# ble112_shield.net
KiCad netlist of a schematic drawn in EAGLE
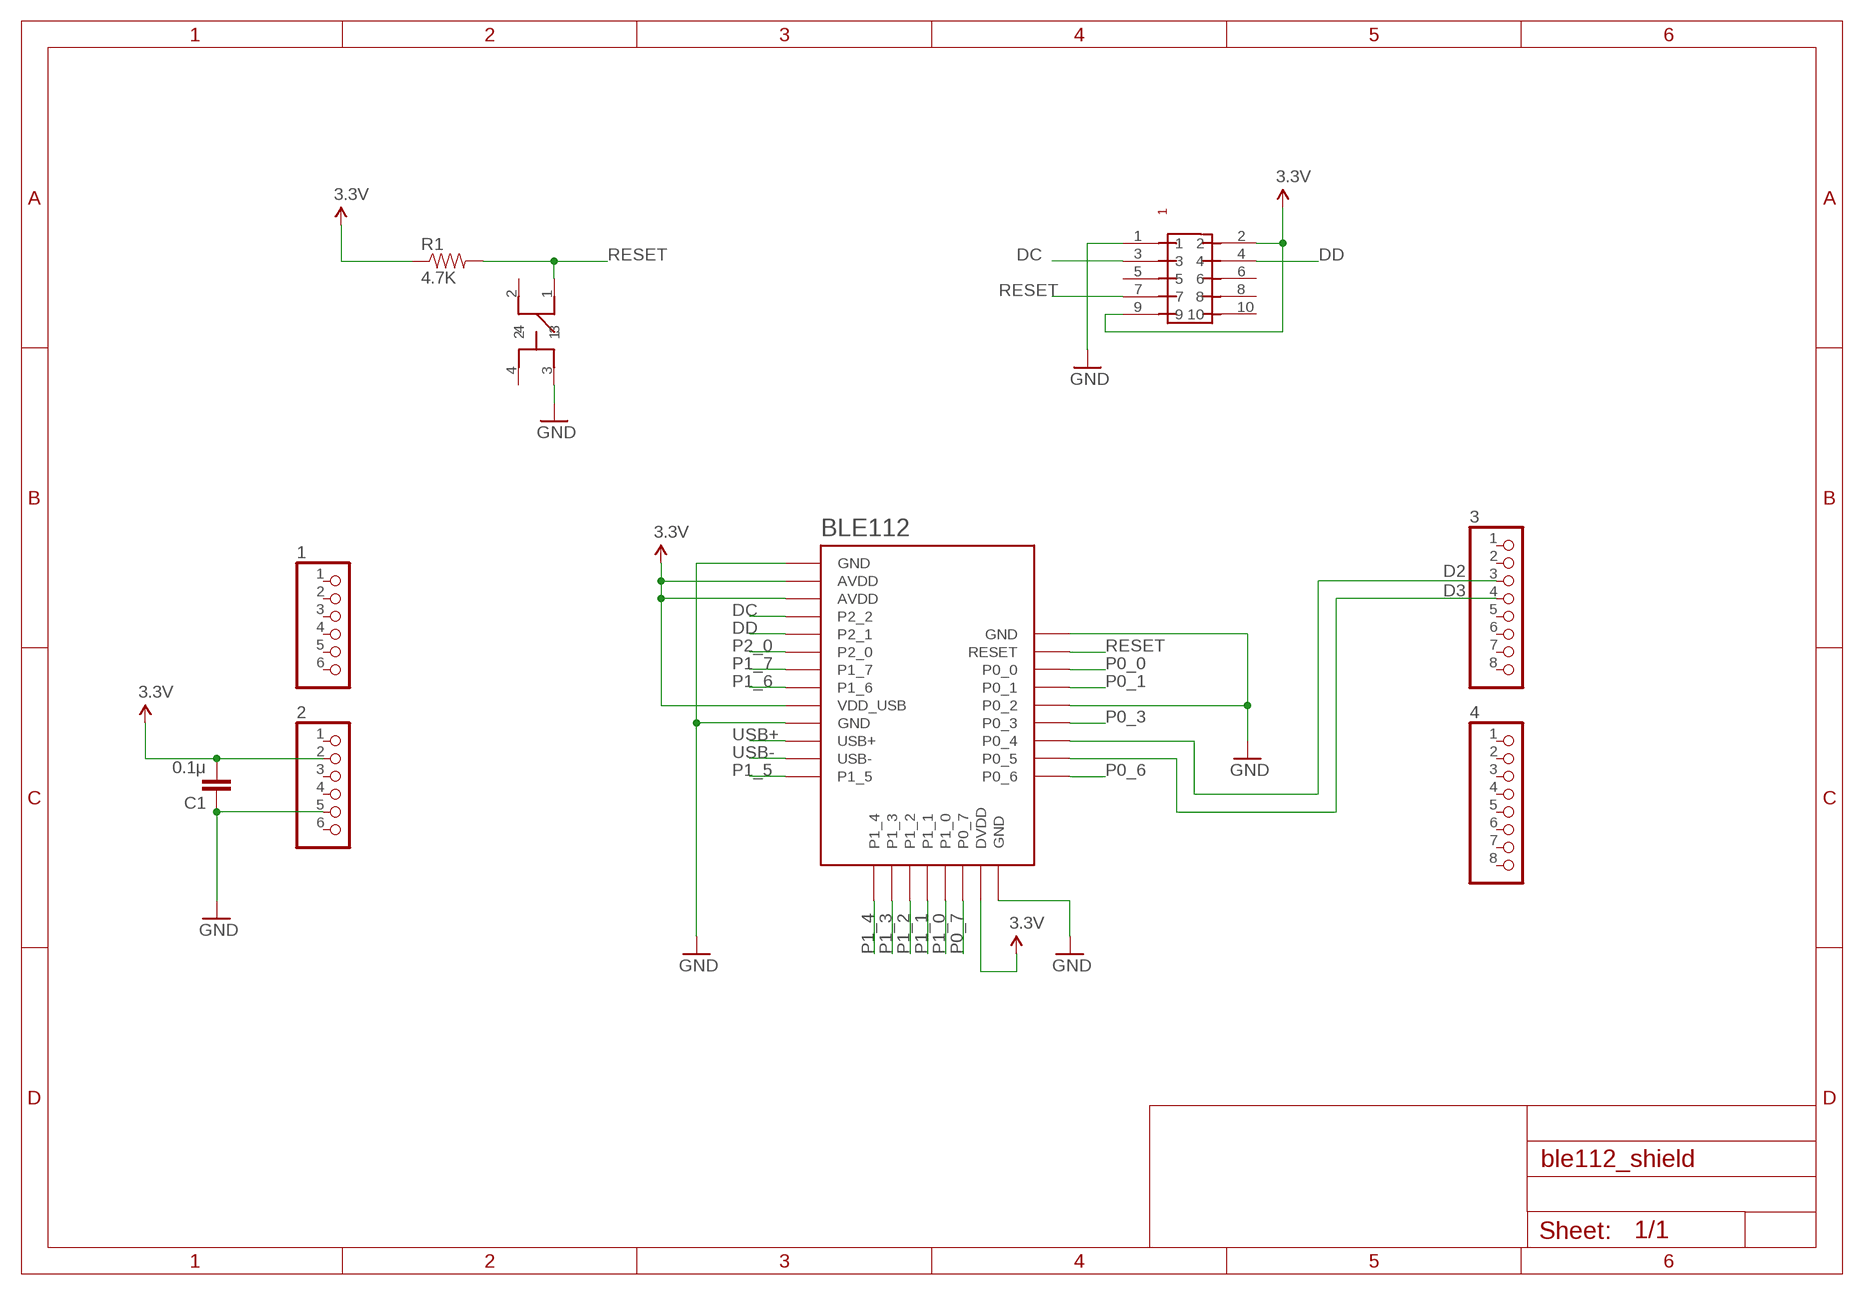
[diagram p0: schematic, sheet 1]

(export (version "E")
  (design (tool "Eeschema 10.0.6"))
  (components
    (comp (ref "1")
      (value "PINHD-1X6CB")
      (footprint "eagle-import:1X06-CLEANBIG")
      (libsource (lib "eagle-import") (part "PINHD-1X6CB"))
    )
    (comp (ref "2")
      (value "PINHD-1X6CB")
      (footprint "eagle-import:1X06-CLEANBIG")
      (libsource (lib "eagle-import") (part "PINHD-1X6CB"))
    )
    (comp (ref "3")
      (value "PINHD-1X8CLEANBIG")
      (footprint "eagle-import:1X08-CLEANBIG")
      (libsource (lib "eagle-import") (part "PINHD-1X8CLEANBIG"))
    )
    (comp (ref "4")
      (value "PINHD-1X8CLEANBIG")
      (footprint "eagle-import:1X08-CLEANBIG")
      (libsource (lib "eagle-import") (part "PINHD-1X8CLEANBIG"))
    )
    (comp (ref "BLE112")
      (value "SF-BLUEGIGA_BLE112-A-VISUAL")
      (footprint "eagle-import:SF-BLUEGIGA_BLE112-A")
      (libsource (lib "eagle-import") (part "SF-BLUEGIGA_BLE112-A-VISUAL"))
    )
    (comp (ref "C1")
      (value "0.1μ")
      (footprint "eagle-import:0603-CAP")
      (libsource (lib "eagle-import") (part "CAP0603-CAP"))
    )
    (comp (ref "R1")
      (value "4.7K")
      (footprint "eagle-import:0603-RES")
      (libsource (lib "eagle-import") (part "RESISTOR0603-RES"))
    )
    (comp (ref "U$1")
      (value "PIN-HEADER-SMT(1.27MM)2X5")
      (footprint "eagle-import:PIN-HEADER-SMT(1.27MM)2X5")
      (libsource (lib "eagle-import") (part "PIN-HEADER-SMT(1.27MM)2X5"))
    )
    (comp (ref "U$4")
      (value "SWITCH-LS6J2M-T")
      (footprint "eagle-import:SWICTH-LS6J2M-T")
      (libsource (lib "eagle-import") (part "SWITCH-LS6J2M-T"))
    )
  )
  (nets
    (net (code "1") (name "/D2") (class "Default")
      (node (ref "3") (pin "3") (pinfunction "3_3") (pintype "passive"))
      (node (ref "BLE112") (pin "P0_4") (pinfunction "P0_4_P0_4") (pintype "bidirectional"))
    )
    (net (code "2") (name "/D3") (class "Default")
      (node (ref "3") (pin "4") (pinfunction "4_4") (pintype "passive"))
      (node (ref "BLE112") (pin "P0_5") (pinfunction "P0_5_P0_5") (pintype "bidirectional"))
    )
    (net (code "3") (name "/DC") (class "Default")
      (node (ref "BLE112") (pin "P2_2") (pinfunction "P2_2_P2_2") (pintype "bidirectional"))
      (node (ref "U$1") (pin "3") (pinfunction "3_3") (pintype "bidirectional"))
    )
    (net (code "4") (name "/DD") (class "Default")
      (node (ref "BLE112") (pin "P2_1") (pinfunction "P2_1_P2_1") (pintype "bidirectional"))
      (node (ref "U$1") (pin "4") (pinfunction "4_4") (pintype "bidirectional"))
    )
    (net (code "5") (name "/P0_0") (class "Default")
      (node (ref "BLE112") (pin "P0_0") (pinfunction "P0_0_P0_0") (pintype "bidirectional"))
    )
    (net (code "6") (name "/P0_1") (class "Default")
      (node (ref "BLE112") (pin "P0_1") (pinfunction "P0_1_P0_1") (pintype "bidirectional"))
    )
    (net (code "7") (name "/P0_3") (class "Default")
      (node (ref "BLE112") (pin "P0_3") (pinfunction "P0_3_P0_3") (pintype "bidirectional"))
    )
    (net (code "8") (name "/P0_6") (class "Default")
      (node (ref "BLE112") (pin "P0_6") (pinfunction "P0_6_P0_6") (pintype "bidirectional"))
    )
    (net (code "9") (name "/P0_7") (class "Default")
      (node (ref "BLE112") (pin "P0_7") (pinfunction "P0_7_P0_7") (pintype "bidirectional"))
    )
    (net (code "10") (name "/P1_0") (class "Default")
      (node (ref "BLE112") (pin "P1_0") (pinfunction "P1_0_P1_0") (pintype "bidirectional"))
    )
    (net (code "11") (name "/P1_1") (class "Default")
      (node (ref "BLE112") (pin "P1_1") (pinfunction "P1_1_P1_1") (pintype "bidirectional"))
    )
    (net (code "12") (name "/P1_2") (class "Default")
      (node (ref "BLE112") (pin "P1_2") (pinfunction "P1_2_P1_2") (pintype "bidirectional"))
    )
    (net (code "13") (name "/P1_3") (class "Default")
      (node (ref "BLE112") (pin "P1_3") (pinfunction "P1_3_P1_3") (pintype "bidirectional"))
    )
    (net (code "14") (name "/P1_4") (class "Default")
      (node (ref "BLE112") (pin "P1_4") (pinfunction "P1_4_P1_4") (pintype "bidirectional"))
    )
    (net (code "15") (name "/P1_5") (class "Default")
      (node (ref "BLE112") (pin "P1_5") (pinfunction "P1_5_P1_5") (pintype "bidirectional"))
    )
    (net (code "16") (name "/P1_6") (class "Default")
      (node (ref "BLE112") (pin "P1_6") (pinfunction "P1_6_P1_6") (pintype "bidirectional"))
    )
    (net (code "17") (name "/P1_7") (class "Default")
      (node (ref "BLE112") (pin "P1_7") (pinfunction "P1_7_P1_7") (pintype "bidirectional"))
    )
    (net (code "18") (name "/P2_0") (class "Default")
      (node (ref "BLE112") (pin "P2_0") (pinfunction "P2_0_P2_0") (pintype "bidirectional"))
    )
    (net (code "19") (name "/RESET") (class "Default")
      (node (ref "BLE112") (pin "RESET") (pinfunction "RESET_RESET") (pintype "input"))
      (node (ref "R1") (pin "2") (pinfunction "2_2") (pintype "passive"))
      (node (ref "U$1") (pin "7") (pinfunction "7_7") (pintype "bidirectional"))
      (node (ref "U$4") (pin "1") (pinfunction "1_1") (pintype "bidirectional"))
    )
    (net (code "20") (name "/USB+") (class "Default")
      (node (ref "BLE112") (pin "USB+") (pinfunction "USB+_USB+") (pintype "bidirectional"))
    )
    (net (code "21") (name "/USB-") (class "Default")
      (node (ref "BLE112") (pin "USB-") (pinfunction "USB-_USB-") (pintype "bidirectional"))
    )
    (net (code "22") (name "3.3V") (class "Default")
      (node (ref "2") (pin "2") (pinfunction "2_2") (pintype "passive"))
      (node (ref "BLE112") (pin "AVDD1") (pinfunction "AVDD_AVDD1") (pintype "power_in"))
      (node (ref "BLE112") (pin "AVDD2") (pinfunction "AVDD_AVDD2") (pintype "power_in"))
      (node (ref "BLE112") (pin "DVDD") (pinfunction "DVDD_DVDD") (pintype "power_in"))
      (node (ref "BLE112") (pin "VDD_USB") (pinfunction "VDD_USB_VDD_USB") (pintype "power_in"))
      (node (ref "C1") (pin "2") (pinfunction "2_2") (pintype "passive"))
      (node (ref "R1") (pin "1") (pinfunction "1_1") (pintype "passive"))
      (node (ref "U$1") (pin "2") (pinfunction "2_2") (pintype "bidirectional"))
      (node (ref "U$1") (pin "9") (pinfunction "9_9") (pintype "bidirectional"))
    )
    (net (code "23") (name "GND") (class "Default")
      (node (ref "2") (pin "5") (pinfunction "5_5") (pintype "passive"))
      (node (ref "BLE112") (pin "GND1") (pinfunction "GND_GND1") (pintype "power_in"))
      (node (ref "BLE112") (pin "GND2") (pinfunction "GND_GND2") (pintype "power_in"))
      (node (ref "BLE112") (pin "GND3") (pinfunction "GND_GND3") (pintype "power_in"))
      (node (ref "BLE112") (pin "GND4") (pinfunction "GND_GND4") (pintype "power_in"))
      (node (ref "BLE112") (pin "P0_2") (pinfunction "P0_2_P0_2") (pintype "bidirectional"))
      (node (ref "C1") (pin "1") (pinfunction "1_1") (pintype "passive"))
      (node (ref "U$1") (pin "1") (pinfunction "1_1") (pintype "bidirectional"))
      (node (ref "U$4") (pin "3") (pinfunction "3_3") (pintype "bidirectional"))
    )
    (net (code "24") (name "unconnected-(1-Pad1)") (class "Default")
      (node (ref "1") (pin "1") (pinfunction "1_1") (pintype "passive"))
    )
    (net (code "25") (name "unconnected-(1-Pad2)") (class "Default")
      (node (ref "1") (pin "2") (pinfunction "2_2") (pintype "passive"))
    )
    (net (code "26") (name "unconnected-(1-Pad3)") (class "Default")
      (node (ref "1") (pin "3") (pinfunction "3_3") (pintype "passive"))
    )
    (net (code "27") (name "unconnected-(1-Pad4)") (class "Default")
      (node (ref "1") (pin "4") (pinfunction "4_4") (pintype "passive"))
    )
    (net (code "28") (name "unconnected-(1-Pad5)") (class "Default")
      (node (ref "1") (pin "5") (pinfunction "5_5") (pintype "passive"))
    )
    (net (code "29") (name "unconnected-(1-Pad6)") (class "Default")
      (node (ref "1") (pin "6") (pinfunction "6_6") (pintype "passive"))
    )
    (net (code "30") (name "unconnected-(2-Pad1)") (class "Default")
      (node (ref "2") (pin "1") (pinfunction "1_1") (pintype "passive"))
    )
    (net (code "31") (name "unconnected-(2-Pad3)") (class "Default")
      (node (ref "2") (pin "3") (pinfunction "3_3") (pintype "passive"))
    )
    (net (code "32") (name "unconnected-(2-Pad4)") (class "Default")
      (node (ref "2") (pin "4") (pinfunction "4_4") (pintype "passive"))
    )
    (net (code "33") (name "unconnected-(2-Pad6)") (class "Default")
      (node (ref "2") (pin "6") (pinfunction "6_6") (pintype "passive"))
    )
    (net (code "34") (name "unconnected-(3-Pad1)") (class "Default")
      (node (ref "3") (pin "1") (pinfunction "1_1") (pintype "passive"))
    )
    (net (code "35") (name "unconnected-(3-Pad2)") (class "Default")
      (node (ref "3") (pin "2") (pinfunction "2_2") (pintype "passive"))
    )
    (net (code "36") (name "unconnected-(3-Pad5)") (class "Default")
      (node (ref "3") (pin "5") (pinfunction "5_5") (pintype "passive"))
    )
    (net (code "37") (name "unconnected-(3-Pad6)") (class "Default")
      (node (ref "3") (pin "6") (pinfunction "6_6") (pintype "passive"))
    )
    (net (code "38") (name "unconnected-(3-Pad7)") (class "Default")
      (node (ref "3") (pin "7") (pinfunction "7_7") (pintype "passive"))
    )
    (net (code "39") (name "unconnected-(3-Pad8)") (class "Default")
      (node (ref "3") (pin "8") (pinfunction "8_8") (pintype "passive"))
    )
    (net (code "40") (name "unconnected-(4-Pad1)") (class "Default")
      (node (ref "4") (pin "1") (pinfunction "1_1") (pintype "passive"))
    )
    (net (code "41") (name "unconnected-(4-Pad2)") (class "Default")
      (node (ref "4") (pin "2") (pinfunction "2_2") (pintype "passive"))
    )
    (net (code "42") (name "unconnected-(4-Pad3)") (class "Default")
      (node (ref "4") (pin "3") (pinfunction "3_3") (pintype "passive"))
    )
    (net (code "43") (name "unconnected-(4-Pad4)") (class "Default")
      (node (ref "4") (pin "4") (pinfunction "4_4") (pintype "passive"))
    )
    (net (code "44") (name "unconnected-(4-Pad5)") (class "Default")
      (node (ref "4") (pin "5") (pinfunction "5_5") (pintype "passive"))
    )
    (net (code "45") (name "unconnected-(4-Pad6)") (class "Default")
      (node (ref "4") (pin "6") (pinfunction "6_6") (pintype "passive"))
    )
    (net (code "46") (name "unconnected-(4-Pad7)") (class "Default")
      (node (ref "4") (pin "7") (pinfunction "7_7") (pintype "passive"))
    )
    (net (code "47") (name "unconnected-(4-Pad8)") (class "Default")
      (node (ref "4") (pin "8") (pinfunction "8_8") (pintype "passive"))
    )
    (net (code "48") (name "unconnected-(U$1-Pad5)") (class "Default")
      (node (ref "U$1") (pin "5") (pinfunction "5_5") (pintype "bidirectional"))
    )
    (net (code "49") (name "unconnected-(U$1-Pad6)") (class "Default")
      (node (ref "U$1") (pin "6") (pinfunction "6_6") (pintype "bidirectional"))
    )
    (net (code "50") (name "unconnected-(U$1-Pad8)") (class "Default")
      (node (ref "U$1") (pin "8") (pinfunction "8_8") (pintype "bidirectional"))
    )
    (net (code "51") (name "unconnected-(U$1-Pad10)") (class "Default")
      (node (ref "U$1") (pin "10") (pinfunction "10_10") (pintype "bidirectional"))
    )
    (net (code "52") (name "unconnected-(U$4-Pad2)") (class "Default")
      (node (ref "U$4") (pin "2") (pinfunction "2_2") (pintype "bidirectional"))
    )
    (net (code "53") (name "unconnected-(U$4-Pad4)") (class "Default")
      (node (ref "U$4") (pin "4") (pinfunction "4_4") (pintype "bidirectional"))
    )
  )
)
